# voltage_mode_preamplifier.net
KiCad netlist of a schematic drawn in Altium Designer
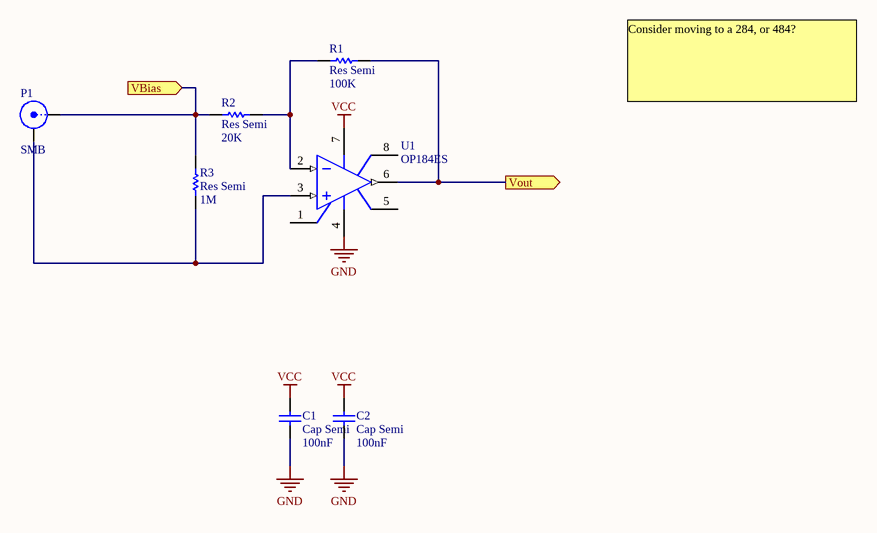
[diagram p0: voltage_mode_preamplifier.SchDoc]

(export (version "E")
  (design (tool "Eeschema 10.0.6"))
  (components
    (comp (ref "C1")
      (value "Cap Semi")
      (footprint "C0805")
      (description "Capacitor (Semiconductor SIM Model)")
      (fields (field (name "ALTIUM_VALUE") "100nF") (field (name "PUBLISHER") "Altium Limited"))
      (libsource (lib "Miscellaneous Devices") (part "Cap Semi"))
    )
    (comp (ref "C2")
      (value "Cap Semi")
      (footprint "C0805")
      (description "Capacitor (Semiconductor SIM Model)")
      (fields (field (name "ALTIUM_VALUE") "100nF") (field (name "PUBLISHER") "Altium Limited"))
      (libsource (lib "Miscellaneous Devices") (part "Cap Semi"))
    )
    (comp (ref "P1")
      (value "SMB")
      (footprint "SMB_V-RJ45")
      (description "SMB Straight Connector")
      (fields (field (name "PUBLISHER") "Altium Limited"))
      (libsource (lib "Miscellaneous Connectors") (part "SMB"))
    )
    (comp (ref "R1")
      (value "Res Semi")
      (footprint "RESC2012L")
      (description "Semiconductor Resistor")
      (fields (field (name "ALTIUM_VALUE") "100K") (field (name "PUBLISHER") "Altium Limited"))
      (libsource (lib "Miscellaneous Devices") (part "Res Semi"))
    )
    (comp (ref "R2")
      (value "Res Semi")
      (footprint "RESC2012L")
      (description "Semiconductor Resistor")
      (fields (field (name "ALTIUM_VALUE") "20K") (field (name "PUBLISHER") "Altium Limited"))
      (libsource (lib "Miscellaneous Devices") (part "Res Semi"))
    )
    (comp (ref "R3")
      (value "Res Semi")
      (footprint "RESC2012L")
      (description "Semiconductor Resistor")
      (fields (field (name "ALTIUM_VALUE") "1M") (field (name "PUBLISHER") "Altium Limited"))
      (libsource (lib "Miscellaneous Devices") (part "Res Semi"))
    )
    (comp (ref "U1")
      (value "OP184ES")
      (footprint "SO-8_N")
      (description "Precision Rail-to-Rail Input and Ouput Operational Amplifier")
      (fields (field (name "PUBLISHER") "Altium Limited"))
      (libsource (lib "AD Operational Amplifier") (part "OP184ES"))
    )
  )
  (nets
    (net (code "1") (name "/VBias") (class "Default")
      (node (ref "P1") (pin "1") (pinfunction "X_1") (pintype "passive"))
      (node (ref "R2") (pin "1") (pinfunction "1_1") (pintype "passive"))
      (node (ref "R3") (pin "2") (pinfunction "2_2") (pintype "passive"))
    )
    (net (code "2") (name "/Vout") (class "Default")
      (node (ref "R1") (pin "2") (pinfunction "2_2") (pintype "passive"))
      (node (ref "U1") (pin "6") (pinfunction "OUT_6") (pintype "output"))
    )
    (net (code "3") (name "GND") (class "Default")
      (node (ref "C1") (pin "1") (pinfunction "1_1") (pintype "passive"))
      (node (ref "C2") (pin "1") (pinfunction "1_1") (pintype "passive"))
      (node (ref "U1") (pin "4") (pinfunction "V-_4") (pintype "power_in"))
    )
    (net (code "4") (name "Net-(P1-Y)") (class "Default")
      (node (ref "P1") (pin "2") (pinfunction "Y_2") (pintype "passive"))
      (node (ref "R3") (pin "1") (pinfunction "1_1") (pintype "passive"))
      (node (ref "U1") (pin "3") (pinfunction "IN+_3") (pintype "input"))
    )
    (net (code "5") (name "Net-(U1-IN-)") (class "Default")
      (node (ref "R1") (pin "1") (pinfunction "1_1") (pintype "passive"))
      (node (ref "R2") (pin "2") (pinfunction "2_2") (pintype "passive"))
      (node (ref "U1") (pin "2") (pinfunction "IN-_2") (pintype "input"))
    )
    (net (code "6") (name "VCC") (class "Default")
      (node (ref "C1") (pin "2") (pinfunction "2_2") (pintype "passive"))
      (node (ref "C2") (pin "2") (pinfunction "2_2") (pintype "passive"))
      (node (ref "U1") (pin "7") (pinfunction "V+_7") (pintype "power_in"))
    )
    (net (code "7") (name "unconnected-(U1-NC-Pad8)") (class "Default")
      (node (ref "U1") (pin "8") (pinfunction "NC_8") (pintype "passive"))
    )
    (net (code "8") (name "unconnected-(U1-NUL-Pad1)") (class "Default")
      (node (ref "U1") (pin "1") (pinfunction "NUL_1") (pintype "passive"))
    )
    (net (code "9") (name "unconnected-(U1-NUL-Pad5)") (class "Default")
      (node (ref "U1") (pin "5") (pinfunction "NUL_5") (pintype "passive"))
    )
  )
)
